# INPUT.net
KiCad netlist of a schematic drawn in Altium Designer
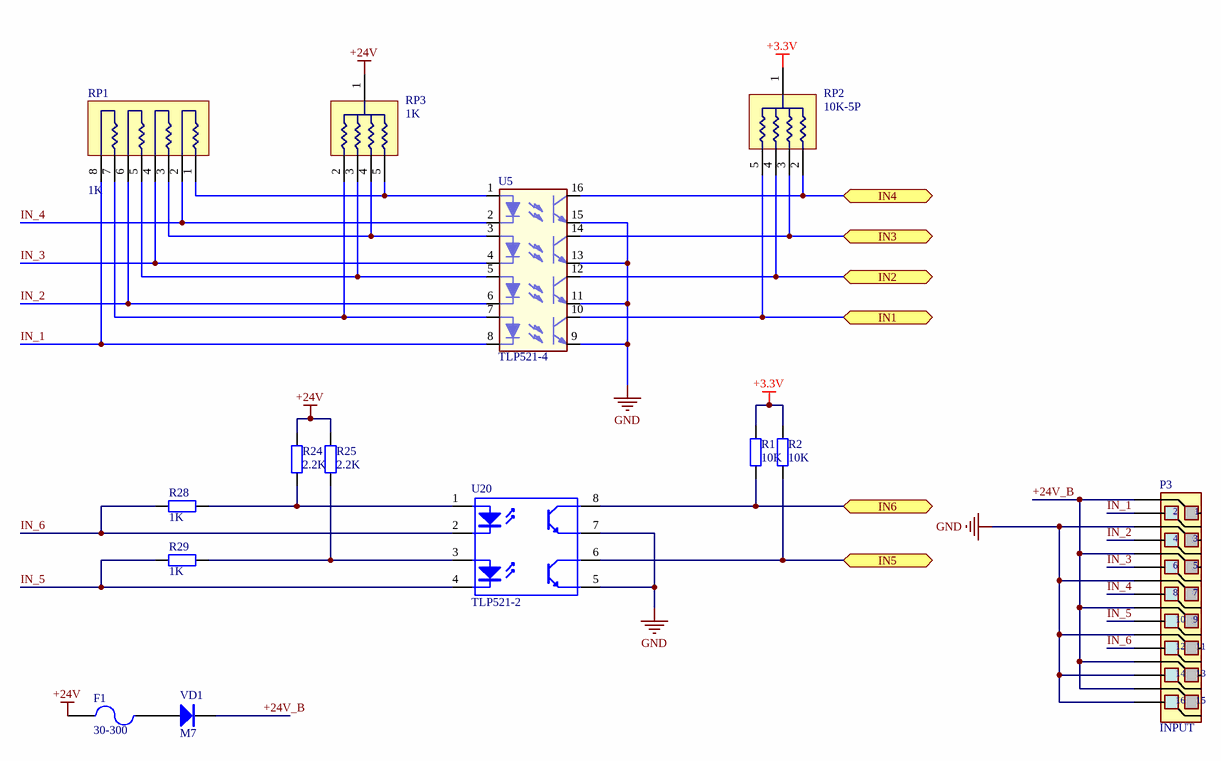
[diagram p0: INPUT.SchDoc]

(export (version "E")
  (design (tool "Eeschema 10.0.6"))
  (components
    (comp (ref "F1")
      (value "30-300")
      (footprint "FU 1812")
      (description "Fuse")
      (fields (field (name "PUBLISHER") "Altium Limited"))
      (libsource (lib "YXF_ComponentLibrary") (part "Fuse 2"))
    )
    (comp (ref "P3")
      (value "INPUT")
      (footprint "557-2x8")
      (description "接插件")
      (libsource (lib "Connectors") (part "557-2x8"))
    )
    (comp (ref "R1") (value "10K") (footprint "R 0805") (libsource (lib "any") (part "Res1")))
    (comp (ref "R2") (value "10K") (footprint "R 0805") (libsource (lib "any") (part "Res1")))
    (comp (ref "R24") (value "2.2K") (footprint "R 0805") (libsource (lib "any") (part "Res1")))
    (comp (ref "R25") (value "2.2K") (footprint "R 0805") (libsource (lib "any") (part "Res1")))
    (comp (ref "R28") (value "1K") (footprint "R 0805") (libsource (lib "") (part "Res1_1")))
    (comp (ref "R29") (value "1K") (footprint "R 0805") (libsource (lib "") (part "Res1_1")))
    (comp (ref "RP1") (value "1K") (footprint "HDR1X8_1") (libsource (lib "any") (part "Res_Pack4_SIP8")))
    (comp (ref "RP2") (value "10K-5P") (footprint "HDR1X5_1") (libsource (lib "") (part "Res4_1")))
    (comp (ref "RP3") (value "1K") (footprint "HDR1X5_1") (libsource (lib "any") (part "Res4")))
    (comp (ref "U5") (value "TLP521-4") (libsource (lib "*") (part "OPTOISOLATOR1_4A")))
    (comp (ref "U20")
      (value "TLP521-2")
      (footprint "DIP8-300_MH")
      (description "2路开关光耦")
      (fields (field (name "版权归属") "源创客"))
      (libsource (lib "传感元件") (part "TLP521-2"))
    )
    (comp (ref "VD1")
      (value "M7")
      (footprint "SMA")
      (description "整流二极管")
      (fields (field (name "版权归属") "源创客"))
      (libsource (lib "二极管-整流桥") (part "M7"))
    )
  )
  (nets
    (net (code "1") (name "+3.3V") (class "Default")
      (node (ref "R1") (pin "1") (pinfunction "1_1") (pintype "passive"))
      (node (ref "R2") (pin "1") (pinfunction "1_1") (pintype "passive"))
      (node (ref "RP2") (pin "1") (pintype "passive"))
    )
    (net (code "2") (name "+24V") (class "Default")
      (node (ref "F1") (pin "1") (pinfunction "1_1") (pintype "passive"))
      (node (ref "R24") (pin "1") (pinfunction "1_1") (pintype "passive"))
      (node (ref "R25") (pin "1") (pinfunction "1_1") (pintype "passive"))
      (node (ref "RP3") (pin "1") (pintype "passive"))
    )
    (net (code "3") (name "/+24V_B") (class "Default")
      (node (ref "P3") (pin "1") (pinfunction "1_1") (pintype "passive"))
      (node (ref "P3") (pin "13") (pinfunction "13_13") (pintype "passive"))
      (node (ref "P3") (pin "15") (pinfunction "15_15") (pintype "passive"))
      (node (ref "P3") (pin "5") (pinfunction "5_5") (pintype "passive"))
      (node (ref "P3") (pin "9") (pinfunction "9_9") (pintype "passive"))
      (node (ref "VD1") (pin "2") (pinfunction "K_2") (pintype "passive"))
    )
    (net (code "4") (name "/IN1") (class "Default")
      (node (ref "RP2") (pin "5") (pintype "passive"))
      (node (ref "U5") (pin "10") (pinfunction "10_10") (pintype "passive"))
    )
    (net (code "5") (name "/IN2") (class "Default")
      (node (ref "RP2") (pin "4") (pintype "passive"))
      (node (ref "U5") (pin "12") (pinfunction "12_12") (pintype "passive"))
    )
    (net (code "6") (name "/IN3") (class "Default")
      (node (ref "RP2") (pin "3") (pintype "passive"))
      (node (ref "U5") (pin "14") (pinfunction "14_14") (pintype "passive"))
    )
    (net (code "7") (name "/IN4") (class "Default")
      (node (ref "RP2") (pin "2") (pintype "passive"))
      (node (ref "U5") (pin "16") (pinfunction "16_16") (pintype "passive"))
    )
    (net (code "8") (name "/IN5") (class "Default")
      (node (ref "R2") (pin "2") (pinfunction "2_2") (pintype "passive"))
      (node (ref "U20") (pin "6") (pinfunction "2C_6") (pintype "passive"))
    )
    (net (code "9") (name "/IN6") (class "Default")
      (node (ref "R1") (pin "2") (pinfunction "2_2") (pintype "passive"))
      (node (ref "U20") (pin "8") (pinfunction "1C_8") (pintype "passive"))
    )
    (net (code "10") (name "/IN_1") (class "Default")
      (node (ref "P3") (pin "2") (pinfunction "2_2") (pintype "passive"))
      (node (ref "RP1") (pin "8") (pintype "passive"))
      (node (ref "U5") (pin "8") (pinfunction "8_8") (pintype "passive"))
    )
    (net (code "11") (name "/IN_2") (class "Default")
      (node (ref "P3") (pin "4") (pinfunction "4_4") (pintype "passive"))
      (node (ref "RP1") (pin "6") (pintype "passive"))
      (node (ref "U5") (pin "6") (pinfunction "6_6") (pintype "passive"))
    )
    (net (code "12") (name "/IN_3") (class "Default")
      (node (ref "P3") (pin "6") (pinfunction "6_6") (pintype "passive"))
      (node (ref "RP1") (pin "4") (pintype "passive"))
      (node (ref "U5") (pin "4") (pinfunction "4_4") (pintype "passive"))
    )
    (net (code "13") (name "/IN_4") (class "Default")
      (node (ref "P3") (pin "8") (pinfunction "8_8") (pintype "passive"))
      (node (ref "RP1") (pin "2") (pintype "passive"))
      (node (ref "U5") (pin "2") (pinfunction "2_2") (pintype "passive"))
    )
    (net (code "14") (name "/IN_5") (class "Default")
      (node (ref "P3") (pin "10") (pinfunction "10_10") (pintype "passive"))
      (node (ref "R29") (pin "1") (pinfunction "1_1") (pintype "passive"))
      (node (ref "U20") (pin "4") (pinfunction "2K_4") (pintype "passive"))
    )
    (net (code "15") (name "/IN_6") (class "Default")
      (node (ref "P3") (pin "12") (pinfunction "12_12") (pintype "passive"))
      (node (ref "R28") (pin "1") (pinfunction "1_1") (pintype "passive"))
      (node (ref "U20") (pin "2") (pinfunction "1K_2") (pintype "passive"))
    )
    (net (code "16") (name "GND") (class "Default")
      (node (ref "P3") (pin "11") (pinfunction "11_11") (pintype "passive"))
      (node (ref "P3") (pin "14") (pinfunction "14_14") (pintype "passive"))
      (node (ref "P3") (pin "16") (pinfunction "16_16") (pintype "passive"))
      (node (ref "P3") (pin "3") (pinfunction "3_3") (pintype "passive"))
      (node (ref "P3") (pin "7") (pinfunction "7_7") (pintype "passive"))
      (node (ref "U20") (pin "5") (pinfunction "2E_5") (pintype "passive"))
      (node (ref "U20") (pin "7") (pinfunction "1E_7") (pintype "passive"))
      (node (ref "U5") (pin "11") (pinfunction "11_11") (pintype "passive"))
      (node (ref "U5") (pin "13") (pinfunction "13_13") (pintype "passive"))
      (node (ref "U5") (pin "15") (pinfunction "15_15") (pintype "passive"))
      (node (ref "U5") (pin "9") (pinfunction "9_9") (pintype "passive"))
    )
    (net (code "17") (name "Net-(RP1-Pad1)") (class "Default")
      (node (ref "RP1") (pin "1") (pintype "passive"))
      (node (ref "RP3") (pin "5") (pintype "passive"))
      (node (ref "U5") (pin "1") (pinfunction "1_1") (pintype "passive"))
    )
    (net (code "18") (name "Net-(RP1-Pad3)") (class "Default")
      (node (ref "RP1") (pin "3") (pintype "passive"))
      (node (ref "RP3") (pin "4") (pintype "passive"))
      (node (ref "U5") (pin "3") (pinfunction "3_3") (pintype "passive"))
    )
    (net (code "19") (name "Net-(RP1-Pad5)") (class "Default")
      (node (ref "RP1") (pin "5") (pintype "passive"))
      (node (ref "RP3") (pin "3") (pintype "passive"))
      (node (ref "U5") (pin "5") (pinfunction "5_5") (pintype "passive"))
    )
    (net (code "20") (name "Net-(RP1-Pad7)") (class "Default")
      (node (ref "RP1") (pin "7") (pintype "passive"))
      (node (ref "RP3") (pin "2") (pintype "passive"))
      (node (ref "U5") (pin "7") (pinfunction "7_7") (pintype "passive"))
    )
    (net (code "21") (name "Net-(U20-1A)") (class "Default")
      (node (ref "R24") (pin "2") (pinfunction "2_2") (pintype "passive"))
      (node (ref "R28") (pin "2") (pinfunction "2_2") (pintype "passive"))
      (node (ref "U20") (pin "1") (pinfunction "1A_1") (pintype "passive"))
    )
    (net (code "22") (name "Net-(U20-2A)") (class "Default")
      (node (ref "R25") (pin "2") (pinfunction "2_2") (pintype "passive"))
      (node (ref "R29") (pin "2") (pinfunction "2_2") (pintype "passive"))
      (node (ref "U20") (pin "3") (pinfunction "2A_3") (pintype "passive"))
    )
    (net (code "23") (name "Net-(VD1-A)") (class "Default")
      (node (ref "F1") (pin "2") (pinfunction "2_2") (pintype "passive"))
      (node (ref "VD1") (pin "1") (pinfunction "A_1") (pintype "passive"))
    )
  )
)
